# kapcsrajz.net
KiCad netlist of a schematic drawn in EAGLE
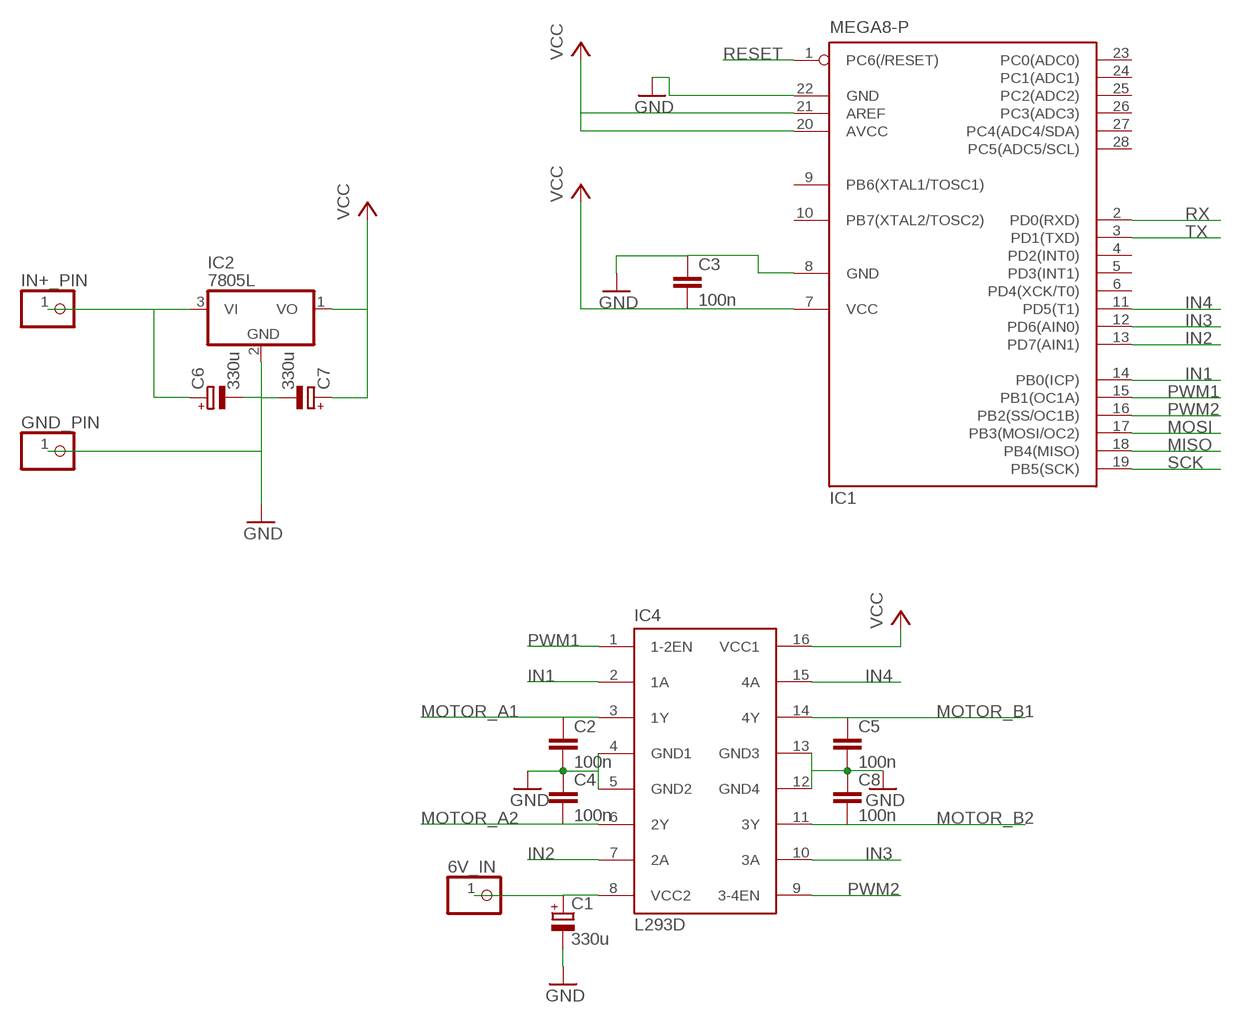
[diagram p0: schematic, sheet 1]
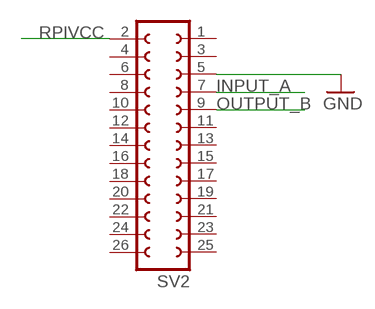
[diagram p1: schematic, sheet 2]
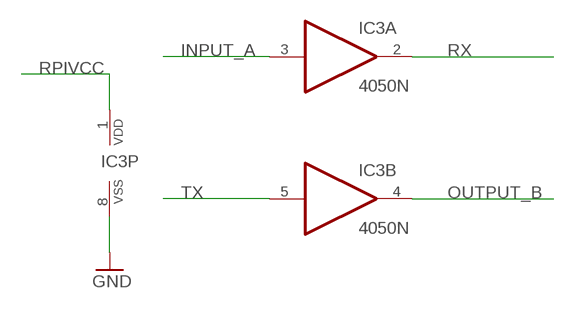
[diagram p2: schematic, sheet 3]
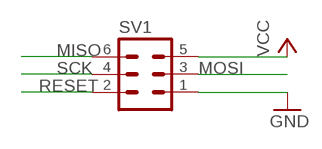
[diagram p3: schematic, sheet 4]
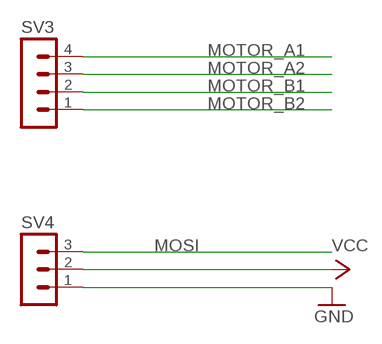
[diagram p4: schematic, sheet 5]

(export (version "E")
  (design (tool "Eeschema 10.0.6"))
  (components
    (comp (ref "SV2")
      (value "FE13-2")
      (footprint "eagle-import:FE13-2")
      (libsource (lib "eagle-import") (part "FE13-2"))
    )
    (comp (ref "6V_IN")
      (value "PINHD-1X1")
      (footprint "eagle-import:1X01")
      (libsource (lib "eagle-import") (part "PINHD-1X1"))
    )
    (comp (ref "C1")
      (value "330u")
      (footprint "eagle-import:E2,5-6E")
      (libsource (lib "eagle-import") (part "CPOL-EUE2,5-6E"))
    )
    (comp (ref "C2")
      (value "100n")
      (footprint "eagle-import:C025-030X050")
      (libsource (lib "eagle-import") (part "C-EU025-030X050"))
    )
    (comp (ref "C3")
      (value "100n")
      (footprint "eagle-import:C025-030X050")
      (libsource (lib "eagle-import") (part "C-EU025-030X050"))
    )
    (comp (ref "C4")
      (value "100n")
      (footprint "eagle-import:C025-030X050")
      (libsource (lib "eagle-import") (part "C-EU025-030X050"))
    )
    (comp (ref "C5")
      (value "100n")
      (footprint "eagle-import:C025-030X050")
      (libsource (lib "eagle-import") (part "C-EU025-030X050"))
    )
    (comp (ref "C6")
      (value "330u")
      (footprint "eagle-import:E2,5-6E")
      (libsource (lib "eagle-import") (part "CPOL-EUE2,5-6E"))
    )
    (comp (ref "C7")
      (value "330u")
      (footprint "eagle-import:E2,5-6E")
      (libsource (lib "eagle-import") (part "CPOL-EUE2,5-6E"))
    )
    (comp (ref "C8")
      (value "100n")
      (footprint "eagle-import:C025-030X050")
      (libsource (lib "eagle-import") (part "C-EU025-030X050"))
    )
    (comp (ref "GND_PIN")
      (value "PINHD-1X1")
      (footprint "eagle-import:1X01")
      (libsource (lib "eagle-import") (part "PINHD-1X1"))
    )
    (comp (ref "IC1")
      (value "MEGA8-P")
      (footprint "eagle-import:DIL28-3")
      (libsource (lib "eagle-import") (part "MEGA8-P"))
    )
    (comp (ref "IC2")
      (value "7805L")
      (footprint "eagle-import:TO92")
      (libsource (lib "eagle-import") (part "78L05"))
    )
    (comp (ref "IC4")
      (value "L293D")
      (footprint "eagle-import:DIL16")
      (libsource (lib "eagle-import") (part "L293D"))
    )
    (comp (ref "IN+_PIN")
      (value "PINHD-1X1")
      (footprint "eagle-import:1X01")
      (libsource (lib "eagle-import") (part "PINHD-1X1"))
    )
    (comp (ref "IC3")
      (value "4050N")
      (footprint "eagle-import:DIL16")
      (libsource (lib "eagle-import") (part "4050N"))
    )
    (comp (ref "SV1")
      (value "MA03-2")
      (footprint "eagle-import:MA03-2")
      (libsource (lib "eagle-import") (part "MA03-2"))
    )
    (comp (ref "SV3")
      (value "MA04-1")
      (footprint "eagle-import:MA04-1")
      (libsource (lib "eagle-import") (part "MA04-1"))
    )
    (comp (ref "SV4")
      (value "MA03-1")
      (footprint "eagle-import:MA03-1")
      (libsource (lib "eagle-import") (part "MA03-1"))
    )
  )
  (nets
    (net (code "1") (name "GND") (class "Default")
      (node (ref "C1") (pin "-") (pinfunction "-_-") (pintype "passive"))
      (node (ref "C2") (pin "2") (pinfunction "2_2") (pintype "passive"))
      (node (ref "C3") (pin "1") (pinfunction "1_1") (pintype "passive"))
      (node (ref "C4") (pin "1") (pinfunction "1_1") (pintype "passive"))
      (node (ref "C5") (pin "2") (pinfunction "2_2") (pintype "passive"))
      (node (ref "C6") (pin "-") (pinfunction "-_-") (pintype "passive"))
      (node (ref "C7") (pin "-") (pinfunction "-_-") (pintype "passive"))
      (node (ref "C8") (pin "1") (pinfunction "1_1") (pintype "passive"))
      (node (ref "GND_PIN") (pin "1") (pinfunction "1_1") (pintype "passive"))
      (node (ref "IC1") (pin "22") (pinfunction "GND_22") (pintype "power_in"))
      (node (ref "IC1") (pin "8") (pinfunction "GND_8") (pintype "power_in"))
      (node (ref "IC2") (pin "2") (pinfunction "GND_2") (pintype "passive"))
      (node (ref "IC3") (pin "8") (pinfunction "VSS_8") (pintype "power_in"))
      (node (ref "IC4") (pin "12") (pinfunction "GND4_12") (pintype "power_in"))
      (node (ref "IC4") (pin "13") (pinfunction "GND3_13") (pintype "power_in"))
      (node (ref "IC4") (pin "4") (pinfunction "GND1_4") (pintype "power_in"))
      (node (ref "IC4") (pin "5") (pinfunction "GND2_5") (pintype "power_in"))
      (node (ref "SV1") (pin "1") (pinfunction "1_1") (pintype "passive"))
      (node (ref "SV2") (pin "5") (pinfunction "5_5") (pintype "passive"))
      (node (ref "SV4") (pin "1") (pinfunction "1_1") (pintype "passive"))
    )
    (net (code "2") (name "IN1") (class "Default")
      (node (ref "IC1") (pin "14") (pinfunction "PB0(ICP)_14") (pintype "bidirectional"))
      (node (ref "IC4") (pin "2") (pinfunction "1A_2") (pintype "input"))
    )
    (net (code "3") (name "IN2") (class "Default")
      (node (ref "IC1") (pin "13") (pinfunction "PD7(AIN1)_13") (pintype "bidirectional"))
      (node (ref "IC4") (pin "7") (pinfunction "2A_7") (pintype "input"))
    )
    (net (code "4") (name "IN3") (class "Default")
      (node (ref "IC1") (pin "12") (pinfunction "PD6(AIN0)_12") (pintype "bidirectional"))
      (node (ref "IC4") (pin "10") (pinfunction "3A_10") (pintype "input"))
    )
    (net (code "5") (name "IN4") (class "Default")
      (node (ref "IC1") (pin "11") (pinfunction "PD5(T1)_11") (pintype "bidirectional"))
      (node (ref "IC4") (pin "15") (pinfunction "4A_15") (pintype "input"))
    )
    (net (code "6") (name "INPUT_A") (class "Default")
      (node (ref "IC3") (pin "3") (pinfunction "I_3") (pintype "input"))
      (node (ref "SV2") (pin "7") (pinfunction "7_7") (pintype "passive"))
    )
    (net (code "7") (name "MISO") (class "Default")
      (node (ref "IC1") (pin "18") (pinfunction "PB4(MISO)_18") (pintype "bidirectional"))
      (node (ref "SV1") (pin "6") (pinfunction "6_6") (pintype "passive"))
    )
    (net (code "8") (name "MOSI") (class "Default")
      (node (ref "IC1") (pin "17") (pinfunction "PB3(MOSI/OC2)_17") (pintype "bidirectional"))
      (node (ref "SV1") (pin "3") (pinfunction "3_3") (pintype "passive"))
      (node (ref "SV4") (pin "3") (pinfunction "3_3") (pintype "passive"))
    )
    (net (code "9") (name "MOTOR_A1") (class "Default")
      (node (ref "C2") (pin "1") (pinfunction "1_1") (pintype "passive"))
      (node (ref "IC4") (pin "3") (pinfunction "1Y_3") (pintype "output"))
      (node (ref "SV3") (pin "4") (pinfunction "4_4") (pintype "passive"))
    )
    (net (code "10") (name "MOTOR_A2") (class "Default")
      (node (ref "C4") (pin "2") (pinfunction "2_2") (pintype "passive"))
      (node (ref "IC4") (pin "6") (pinfunction "2Y_6") (pintype "output"))
      (node (ref "SV3") (pin "3") (pinfunction "3_3") (pintype "passive"))
    )
    (net (code "11") (name "MOTOR_B1") (class "Default")
      (node (ref "C5") (pin "1") (pinfunction "1_1") (pintype "passive"))
      (node (ref "IC4") (pin "14") (pinfunction "4Y_14") (pintype "output"))
      (node (ref "SV3") (pin "2") (pinfunction "2_2") (pintype "passive"))
    )
    (net (code "12") (name "MOTOR_B2") (class "Default")
      (node (ref "C8") (pin "2") (pinfunction "2_2") (pintype "passive"))
      (node (ref "IC4") (pin "11") (pinfunction "3Y_11") (pintype "output"))
      (node (ref "SV3") (pin "1") (pinfunction "1_1") (pintype "passive"))
    )
    (net (code "13") (name "Net-(IC2-VI)") (class "Default")
      (node (ref "C6") (pin "+") (pinfunction "+_+") (pintype "passive"))
      (node (ref "IC2") (pin "3") (pinfunction "VI_3") (pintype "input"))
      (node (ref "IN+_PIN") (pin "1") (pinfunction "1_1") (pintype "passive"))
    )
    (net (code "14") (name "Net-(IC4-VCC2)") (class "Default")
      (node (ref "6V_IN") (pin "1") (pinfunction "1_1") (pintype "passive"))
      (node (ref "C1") (pin "+") (pinfunction "+_+") (pintype "passive"))
      (node (ref "IC4") (pin "8") (pinfunction "VCC2_8") (pintype "power_in"))
    )
    (net (code "15") (name "OUTPUT_B") (class "Default")
      (node (ref "IC3") (pin "4") (pinfunction "O_4") (pintype "output"))
      (node (ref "SV2") (pin "9") (pinfunction "9_9") (pintype "passive"))
    )
    (net (code "16") (name "PWM1") (class "Default")
      (node (ref "IC1") (pin "15") (pinfunction "PB1(OC1A)_15") (pintype "bidirectional"))
      (node (ref "IC4") (pin "1") (pinfunction "1-2EN_1") (pintype "input"))
    )
    (net (code "17") (name "PWM2") (class "Default")
      (node (ref "IC1") (pin "16") (pinfunction "PB2(SS/OC1B)_16") (pintype "bidirectional"))
      (node (ref "IC4") (pin "9") (pinfunction "3-4EN_9") (pintype "input"))
    )
    (net (code "18") (name "RESET") (class "Default")
      (node (ref "IC1") (pin "1") (pinfunction "PC6(/RESET)_1") (pintype "bidirectional"))
      (node (ref "SV1") (pin "2") (pinfunction "2_2") (pintype "passive"))
    )
    (net (code "19") (name "RPIVCC") (class "Default")
      (node (ref "IC3") (pin "1") (pinfunction "VDD_1") (pintype "power_in"))
      (node (ref "SV2") (pin "2") (pinfunction "2_2") (pintype "passive"))
    )
    (net (code "20") (name "RX") (class "Default")
      (node (ref "IC1") (pin "2") (pinfunction "PD0(RXD)_2") (pintype "bidirectional"))
      (node (ref "IC3") (pin "2") (pinfunction "O_2") (pintype "output"))
    )
    (net (code "21") (name "SCK") (class "Default")
      (node (ref "IC1") (pin "19") (pinfunction "PB5(SCK)_19") (pintype "bidirectional"))
      (node (ref "SV1") (pin "4") (pinfunction "4_4") (pintype "passive"))
    )
    (net (code "22") (name "TX") (class "Default")
      (node (ref "IC1") (pin "3") (pinfunction "PD1(TXD)_3") (pintype "bidirectional"))
      (node (ref "IC3") (pin "5") (pinfunction "I_5") (pintype "input"))
    )
    (net (code "23") (name "VCC") (class "Default")
      (node (ref "C3") (pin "2") (pinfunction "2_2") (pintype "passive"))
      (node (ref "C7") (pin "+") (pinfunction "+_+") (pintype "passive"))
      (node (ref "IC1") (pin "20") (pinfunction "AVCC_20") (pintype "power_in"))
      (node (ref "IC1") (pin "21") (pinfunction "AREF_21") (pintype "passive"))
      (node (ref "IC1") (pin "7") (pinfunction "VCC_7") (pintype "power_in"))
      (node (ref "IC2") (pin "1") (pinfunction "VO_1") (pintype "passive"))
      (node (ref "IC4") (pin "16") (pinfunction "VCC1_16") (pintype "power_in"))
      (node (ref "SV1") (pin "5") (pinfunction "5_5") (pintype "passive"))
      (node (ref "SV4") (pin "2") (pinfunction "2_2") (pintype "passive"))
    )
    (net (code "24") (name "unconnected-(IC1-PB6(XTAL1{slash}TOSC1)-Pad9)") (class "Default")
      (node (ref "IC1") (pin "9") (pinfunction "PB6(XTAL1/TOSC1)_9") (pintype "bidirectional"))
    )
    (net (code "25") (name "unconnected-(IC1-PB7(XTAL2{slash}TOSC2)-Pad10)") (class "Default")
      (node (ref "IC1") (pin "10") (pinfunction "PB7(XTAL2/TOSC2)_10") (pintype "bidirectional"))
    )
    (net (code "26") (name "unconnected-(IC1-PC0(ADC0)-Pad23)") (class "Default")
      (node (ref "IC1") (pin "23") (pinfunction "PC0(ADC0)_23") (pintype "bidirectional"))
    )
    (net (code "27") (name "unconnected-(IC1-PC1(ADC1)-Pad24)") (class "Default")
      (node (ref "IC1") (pin "24") (pinfunction "PC1(ADC1)_24") (pintype "bidirectional"))
    )
    (net (code "28") (name "unconnected-(IC1-PC2(ADC2)-Pad25)") (class "Default")
      (node (ref "IC1") (pin "25") (pinfunction "PC2(ADC2)_25") (pintype "bidirectional"))
    )
    (net (code "29") (name "unconnected-(IC1-PC3(ADC3)-Pad26)") (class "Default")
      (node (ref "IC1") (pin "26") (pinfunction "PC3(ADC3)_26") (pintype "bidirectional"))
    )
    (net (code "30") (name "unconnected-(IC1-PC4(ADC4{slash}SDA)-Pad27)") (class "Default")
      (node (ref "IC1") (pin "27") (pinfunction "PC4(ADC4/SDA)_27") (pintype "bidirectional"))
    )
    (net (code "31") (name "unconnected-(IC1-PC5(ADC5{slash}SCL)-Pad28)") (class "Default")
      (node (ref "IC1") (pin "28") (pinfunction "PC5(ADC5/SCL)_28") (pintype "bidirectional"))
    )
    (net (code "32") (name "unconnected-(IC1-PD2(INT0)-Pad4)") (class "Default")
      (node (ref "IC1") (pin "4") (pinfunction "PD2(INT0)_4") (pintype "bidirectional"))
    )
    (net (code "33") (name "unconnected-(IC1-PD3(INT1)-Pad5)") (class "Default")
      (node (ref "IC1") (pin "5") (pinfunction "PD3(INT1)_5") (pintype "bidirectional"))
    )
    (net (code "34") (name "unconnected-(IC1-PD4(XCK{slash}T0)-Pad6)") (class "Default")
      (node (ref "IC1") (pin "6") (pinfunction "PD4(XCK/T0)_6") (pintype "bidirectional"))
    )
    (net (code "35") (name "unconnected-(SV2-Pad1)") (class "Default")
      (node (ref "SV2") (pin "1") (pinfunction "1_1") (pintype "passive"))
    )
    (net (code "36") (name "unconnected-(SV2-Pad3)") (class "Default")
      (node (ref "SV2") (pin "3") (pinfunction "3_3") (pintype "passive"))
    )
    (net (code "37") (name "unconnected-(SV2-Pad4)") (class "Default")
      (node (ref "SV2") (pin "4") (pinfunction "4_4") (pintype "passive"))
    )
    (net (code "38") (name "unconnected-(SV2-Pad6)") (class "Default")
      (node (ref "SV2") (pin "6") (pinfunction "6_6") (pintype "passive"))
    )
    (net (code "39") (name "unconnected-(SV2-Pad8)") (class "Default")
      (node (ref "SV2") (pin "8") (pinfunction "8_8") (pintype "passive"))
    )
    (net (code "40") (name "unconnected-(SV2-Pad10)") (class "Default")
      (node (ref "SV2") (pin "10") (pinfunction "10_10") (pintype "passive"))
    )
    (net (code "41") (name "unconnected-(SV2-Pad11)") (class "Default")
      (node (ref "SV2") (pin "11") (pinfunction "11_11") (pintype "passive"))
    )
    (net (code "42") (name "unconnected-(SV2-Pad12)") (class "Default")
      (node (ref "SV2") (pin "12") (pinfunction "12_12") (pintype "passive"))
    )
    (net (code "43") (name "unconnected-(SV2-Pad13)") (class "Default")
      (node (ref "SV2") (pin "13") (pinfunction "13_13") (pintype "passive"))
    )
    (net (code "44") (name "unconnected-(SV2-Pad14)") (class "Default")
      (node (ref "SV2") (pin "14") (pinfunction "14_14") (pintype "passive"))
    )
    (net (code "45") (name "unconnected-(SV2-Pad15)") (class "Default")
      (node (ref "SV2") (pin "15") (pinfunction "15_15") (pintype "passive"))
    )
    (net (code "46") (name "unconnected-(SV2-Pad16)") (class "Default")
      (node (ref "SV2") (pin "16") (pinfunction "16_16") (pintype "passive"))
    )
    (net (code "47") (name "unconnected-(SV2-Pad17)") (class "Default")
      (node (ref "SV2") (pin "17") (pinfunction "17_17") (pintype "passive"))
    )
    (net (code "48") (name "unconnected-(SV2-Pad18)") (class "Default")
      (node (ref "SV2") (pin "18") (pinfunction "18_18") (pintype "passive"))
    )
    (net (code "49") (name "unconnected-(SV2-Pad19)") (class "Default")
      (node (ref "SV2") (pin "19") (pinfunction "19_19") (pintype "passive"))
    )
    (net (code "50") (name "unconnected-(SV2-Pad20)") (class "Default")
      (node (ref "SV2") (pin "20") (pinfunction "20_20") (pintype "passive"))
    )
    (net (code "51") (name "unconnected-(SV2-Pad21)") (class "Default")
      (node (ref "SV2") (pin "21") (pinfunction "21_21") (pintype "passive"))
    )
    (net (code "52") (name "unconnected-(SV2-Pad22)") (class "Default")
      (node (ref "SV2") (pin "22") (pinfunction "22_22") (pintype "passive"))
    )
    (net (code "53") (name "unconnected-(SV2-Pad23)") (class "Default")
      (node (ref "SV2") (pin "23") (pinfunction "23_23") (pintype "passive"))
    )
    (net (code "54") (name "unconnected-(SV2-Pad24)") (class "Default")
      (node (ref "SV2") (pin "24") (pinfunction "24_24") (pintype "passive"))
    )
    (net (code "55") (name "unconnected-(SV2-Pad25)") (class "Default")
      (node (ref "SV2") (pin "25") (pinfunction "25_25") (pintype "passive"))
    )
    (net (code "56") (name "unconnected-(SV2-Pad26)") (class "Default")
      (node (ref "SV2") (pin "26") (pinfunction "26_26") (pintype "passive"))
    )
  )
)
